# Logic.net
KiCad netlist of a schematic drawn in Altium Designer
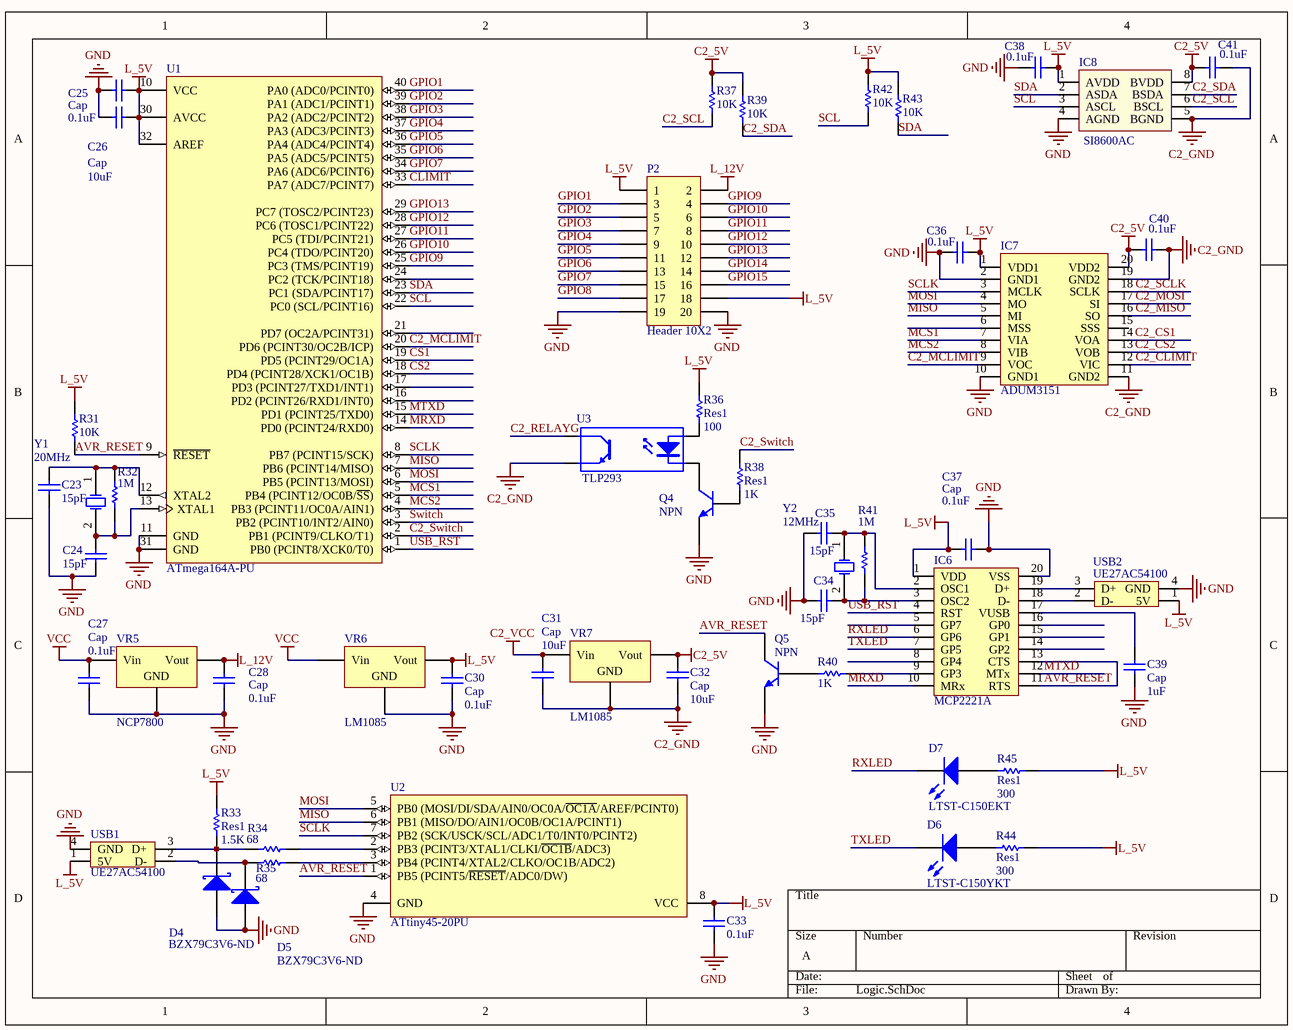
[diagram p0: Logic.SchDoc]

(export (version "E")
  (design (tool "Eeschema 10.0.6"))
  (components
    (comp (ref "C23")
      (value "15pF")
      (footprint "RAD-0.1")
      (description "Capacitor")
      (fields (field (name "Comment") "Cap") (field (name "PUBLISHER") "Altium Limited"))
      (libsource (lib "Miscellaneous Devices") (part "Cap"))
    )
    (comp (ref "C24")
      (value "15pF")
      (footprint "RAD-0.1")
      (description "Capacitor")
      (fields (field (name "Comment") "Cap") (field (name "PUBLISHER") "Altium Limited"))
      (libsource (lib "Miscellaneous Devices") (part "Cap"))
    )
    (comp (ref "C25")
      (value "Cap")
      (footprint "RAD-0.1")
      (description "Capacitor")
      (fields (field (name "ALTIUM_VALUE") "0.1uF") (field (name "PUBLISHER") "Altium Limited"))
      (libsource (lib "Miscellaneous Devices") (part "Cap"))
    )
    (comp (ref "C26")
      (value "Cap")
      (footprint "RAD-0.2")
      (description "Capacitor")
      (fields (field (name "ALTIUM_VALUE") "10uF") (field (name "PUBLISHER") "Altium Limited"))
      (libsource (lib "Miscellaneous Devices") (part "Cap"))
    )
    (comp (ref "C27")
      (value "Cap")
      (footprint "RAD-0.1")
      (description "Capacitor")
      (fields (field (name "ALTIUM_VALUE") "0.1uF") (field (name "PUBLISHER") "Altium Limited"))
      (libsource (lib "Miscellaneous Devices") (part "Cap"))
    )
    (comp (ref "C28")
      (value "Cap")
      (footprint "RAD-0.1")
      (description "Capacitor")
      (fields (field (name "ALTIUM_VALUE") "0.1uF") (field (name "PUBLISHER") "Altium Limited"))
      (libsource (lib "Miscellaneous Devices") (part "Cap"))
    )
    (comp (ref "C30")
      (value "Cap")
      (footprint "RAD-0.1")
      (description "Capacitor")
      (fields (field (name "ALTIUM_VALUE") "0.1uF") (field (name "PUBLISHER") "Altium Limited"))
      (libsource (lib "Power Supply Library") (part "Cap"))
    )
    (comp (ref "C31")
      (value "Cap")
      (footprint "RAD-0.1")
      (description "Capacitor")
      (fields (field (name "ALTIUM_VALUE") "10uF") (field (name "PUBLISHER") "Altium Limited"))
      (libsource (lib "Miscellaneous Devices") (part "Cap"))
    )
    (comp (ref "C32")
      (value "Cap")
      (footprint "RAD-0.1")
      (description "Capacitor")
      (fields (field (name "ALTIUM_VALUE") "10uF") (field (name "PUBLISHER") "Altium Limited"))
      (libsource (lib "Power Supply Library") (part "Cap"))
    )
    (comp (ref "C33")
      (value "0.1uF")
      (footprint "RAD-0.1")
      (description "Capacitor")
      (fields (field (name "Comment") "Cap") (field (name "PUBLISHER") "Altium Limited"))
      (libsource (lib "Miscellaneous Devices") (part "Cap"))
    )
    (comp (ref "C34")
      (value "15pF")
      (footprint "RAD-0.1")
      (description "Capacitor")
      (fields (field (name "Comment") "Cap") (field (name "PUBLISHER") "Altium Limited"))
      (libsource (lib "Miscellaneous Devices") (part "Cap"))
    )
    (comp (ref "C35")
      (value "15pF")
      (footprint "RAD-0.1")
      (description "Capacitor")
      (fields (field (name "Comment") "Cap") (field (name "PUBLISHER") "Altium Limited"))
      (libsource (lib "Miscellaneous Devices") (part "Cap"))
    )
    (comp (ref "C36")
      (value "0.1uF")
      (footprint "RAD-0.1")
      (description "Capacitor")
      (fields (field (name "Comment") "Cap") (field (name "PUBLISHER") "Altium Limited"))
      (libsource (lib "Miscellaneous Devices") (part "Cap"))
    )
    (comp (ref "C37")
      (value "Cap")
      (footprint "RAD-0.1")
      (description "Capacitor")
      (fields (field (name "ALTIUM_VALUE") "0.1uF") (field (name "PUBLISHER") "Altium Limited"))
      (libsource (lib "Miscellaneous Devices") (part "Cap"))
    )
    (comp (ref "C38")
      (value "0.1uF")
      (footprint "RAD-0.1")
      (description "Capacitor")
      (fields (field (name "Comment") "Cap") (field (name "PUBLISHER") "Altium Limited"))
      (libsource (lib "Miscellaneous Devices") (part "Cap"))
    )
    (comp (ref "C39")
      (value "Cap")
      (footprint "RAD-0.1")
      (description "Capacitor")
      (fields (field (name "ALTIUM_VALUE") "1uF") (field (name "PUBLISHER") "Altium Limited"))
      (libsource (lib "Miscellaneous Devices") (part "Cap"))
    )
    (comp (ref "C40")
      (value "0.1uF")
      (footprint "RAD-0.1")
      (description "Capacitor")
      (fields (field (name "Comment") "Cap") (field (name "PUBLISHER") "Altium Limited"))
      (libsource (lib "Miscellaneous Devices") (part "Cap"))
    )
    (comp (ref "C41")
      (value "0.1uF")
      (footprint "RAD-0.1")
      (description "Capacitor")
      (fields (field (name "Comment") "Cap") (field (name "PUBLISHER") "Altium Limited"))
      (libsource (lib "Miscellaneous Devices") (part "Cap"))
    )
    (comp (ref "D4")
      (value "BZX79C3V6-ND")
      (footprint "DO-35")
      (description "Schottky Diode")
      (fields (field (name "PUBLISHER") "Altium Limited"))
      (libsource (lib "Miscellaneous Devices") (part "D Schottky"))
    )
    (comp (ref "D5")
      (value "BZX79C3V6-ND")
      (footprint "DO-35")
      (description "Schottky Diode")
      (fields (field (name "PUBLISHER") "Altium Limited"))
      (libsource (lib "Miscellaneous Devices") (part "D Schottky"))
    )
    (comp (ref "D6")
      (value "LTST-C150YKT")
      (footprint "3.2X1.6X1.1")
      (description "Typical RED, GREEN, YELLOW, AMBER GaAs LED")
      (fields (field (name "PUBLISHER") "Altium Limited"))
      (libsource (lib "Power Supply Library") (part "LED2"))
    )
    (comp (ref "D7")
      (value "LTST-C150EKT")
      (footprint "3.2X1.6X1.1")
      (description "Typical RED, GREEN, YELLOW, AMBER GaAs LED")
      (fields (field (name "PUBLISHER") "Altium Limited"))
      (libsource (lib "Power Supply Library") (part "LED2"))
    )
    (comp (ref "IC6")
      (value "MCP2221A")
      (footprint "20-SO")
      (libsource (lib "Power Supply Library") (part "USB To UART"))
    )
    (comp (ref "IC7")
      (value "ADUM3151")
      (footprint "20-SSOP")
      (libsource (lib "Power Supply Library") (part "SPI Isolator"))
    )
    (comp (ref "IC8")
      (value "SI8600AC")
      (footprint "8-SO")
      (libsource (lib "Power Supply Library") (part "I2C Isolator"))
    )
    (comp (ref "P2")
      (value "Header 10X2")
      (footprint "HDR2X10")
      (description "Header, 10-Pin, Dual row")
      (fields (field (name "PUBLISHER") "Altium Limited"))
      (libsource (lib "Miscellaneous Connectors") (part "Header 10X2"))
    )
    (comp (ref "Q4")
      (value "NPN")
      (footprint "TO-226-AA")
      (description "NPN Bipolar Transistor")
      (fields (field (name "PUBLISHER") "Altium Limited"))
      (libsource (lib "Power Supply Library") (part "NPN"))
    )
    (comp (ref "Q5")
      (value "NPN")
      (footprint "TO-226-AA")
      (description "NPN Bipolar Transistor")
      (fields (field (name "PUBLISHER") "Altium Limited"))
      (libsource (lib "Power Supply Library") (part "NPN"))
    )
    (comp (ref "R31")
      (value "10K")
      (footprint "AXIAL-0.3")
      (description "Resistor")
      (fields (field (name "Comment") "Res1") (field (name "PUBLISHER") "Altium Limited"))
      (libsource (lib "Miscellaneous Devices") (part "Res1"))
    )
    (comp (ref "R32")
      (value "1M")
      (footprint "AXIAL-0.3")
      (description "Resistor")
      (fields (field (name "Comment") "Res1") (field (name "PUBLISHER") "Altium Limited"))
      (libsource (lib "Power Supply Library") (part "Res1"))
    )
    (comp (ref "R33")
      (value "Res1")
      (footprint "AXIAL-0.3")
      (description "Resistor")
      (fields (field (name "ALTIUM_VALUE") "1.5K") (field (name "PUBLISHER") "Altium Limited"))
      (libsource (lib "Power Supply Library") (part "Res1"))
    )
    (comp (ref "R34")
      (value "68")
      (footprint "AXIAL-0.3")
      (description "Resistor")
      (fields (field (name "Comment") "Res1") (field (name "PUBLISHER") "Altium Limited"))
      (libsource (lib "Power Supply Library") (part "Res1"))
    )
    (comp (ref "R35")
      (value "68")
      (footprint "AXIAL-0.3")
      (description "Resistor")
      (fields (field (name "Comment") "Res1") (field (name "PUBLISHER") "Altium Limited"))
      (libsource (lib "Power Supply Library") (part "Res1"))
    )
    (comp (ref "R36")
      (value "Res1")
      (footprint "AXIAL-0.3")
      (description "Resistor")
      (fields (field (name "ALTIUM_VALUE") "100") (field (name "PUBLISHER") "Altium Limited"))
      (libsource (lib "Power Supply Library") (part "Res1"))
    )
    (comp (ref "R37")
      (value "10K")
      (footprint "AXIAL-0.3")
      (description "Resistor")
      (fields (field (name "Comment") "Res1") (field (name "PUBLISHER") "Altium Limited"))
      (libsource (lib "Power Supply Library") (part "Res1"))
    )
    (comp (ref "R38")
      (value "Res1")
      (footprint "AXIAL-0.3")
      (description "Resistor")
      (fields (field (name "ALTIUM_VALUE") "1K") (field (name "PUBLISHER") "Altium Limited"))
      (libsource (lib "Power Supply Library") (part "Res1"))
    )
    (comp (ref "R39")
      (value "10K")
      (footprint "AXIAL-0.3")
      (description "Resistor")
      (fields (field (name "Comment") "Res1") (field (name "PUBLISHER") "Altium Limited"))
      (libsource (lib "Power Supply Library") (part "Res1"))
    )
    (comp (ref "R40")
      (value "1K")
      (footprint "AXIAL-0.3")
      (description "Resistor")
      (fields (field (name "Comment") "Res1") (field (name "PUBLISHER") "Altium Limited"))
      (libsource (lib "Power Supply Library") (part "Res1"))
    )
    (comp (ref "R41")
      (value "1M")
      (footprint "AXIAL-0.3")
      (description "Resistor")
      (fields (field (name "Comment") "Res1") (field (name "PUBLISHER") "Altium Limited"))
      (libsource (lib "Power Supply Library") (part "Res1"))
    )
    (comp (ref "R42")
      (value "10K")
      (footprint "AXIAL-0.3")
      (description "Resistor")
      (fields (field (name "Comment") "Res1") (field (name "PUBLISHER") "Altium Limited"))
      (libsource (lib "Power Supply Library") (part "Res1"))
    )
    (comp (ref "R43")
      (value "10K")
      (footprint "AXIAL-0.3")
      (description "Resistor")
      (fields (field (name "Comment") "Res1") (field (name "PUBLISHER") "Altium Limited"))
      (libsource (lib "Power Supply Library") (part "Res1"))
    )
    (comp (ref "R44")
      (value "Res1")
      (footprint "AXIAL-0.3")
      (description "Resistor")
      (fields (field (name "ALTIUM_VALUE") "300") (field (name "PUBLISHER") "Altium Limited"))
      (libsource (lib "Power Supply Library") (part "Res1"))
    )
    (comp (ref "R45")
      (value "Res1")
      (footprint "AXIAL-0.3")
      (description "Resistor")
      (fields (field (name "ALTIUM_VALUE") "300") (field (name "PUBLISHER") "Altium Limited"))
      (libsource (lib "Power Supply Library") (part "Res1"))
    )
    (comp (ref "U1")
      (value "ATmega164A-PU")
      (footprint "40P6")
      (fields (field (name "PUBLISHER") "Altium Limited"))
      (libsource (lib "Atmel Microcontroller 8-Bit megaAVR") (part "ATmega164A-PU"))
    )
    (comp (ref "U2")
      (value "ATtiny45-20PU")
      (footprint "8P3")
      (fields (field (name "PUBLISHER") "Altium Limited"))
      (libsource (lib "Atmel Microcontroller 8-Bit tinyAVR") (part "ATtiny45-20PU"))
    )
    (comp (ref "U3")
      (value "TLP293")
      (footprint "2-SO")
      (description "4-Pin Phototransistor Optocoupler")
      (fields (field (name "PUBLISHER") "Altium Limited"))
      (libsource (lib "Power Supply Library") (part "Optoisolator1"))
    )
    (comp (ref "USB1") (value "UE27AC54100") (footprint "USB") (libsource (lib "") (part "USB_1")))
    (comp (ref "USB2")
      (value "UE27AC54100")
      (footprint "USB")
      (libsource (lib "Power Supply Library") (part "USB"))
    )
    (comp (ref "VR5")
      (value "NCP7800")
      (footprint "TO220")
      (libsource (lib "Power Supply Library") (part "Voltage Regulator 12V"))
    )
    (comp (ref "VR6")
      (value "LM1085")
      (footprint "TO220")
      (libsource (lib "Power Supply Library") (part "Voltage Regulator 5V"))
    )
    (comp (ref "VR7")
      (value "LM1085")
      (footprint "TO220")
      (libsource (lib "Power Supply Library") (part "Voltage Regulator 5V"))
    )
    (comp (ref "Y1")
      (value "20MHz")
      (footprint "R38")
      (description "Crystal Oscillator")
      (fields (field (name "PUBLISHER") "Altium Limited"))
      (libsource (lib "Miscellaneous Devices") (part "XTAL"))
    )
    (comp (ref "Y2")
      (value "12MHz")
      (footprint "R38")
      (description "Crystal Oscillator")
      (fields (field (name "PUBLISHER") "Altium Limited"))
      (libsource (lib "Miscellaneous Devices") (part "XTAL"))
    )
  )
  (nets
    (net (code "1") (name "/AVR_RESET") (class "Default")
      (node (ref "IC6") (pin "11") (pinfunction "RTS_11") (pintype "passive"))
      (node (ref "IC6") (pin "13") (pinfunction "CTS_13") (pintype "passive"))
      (node (ref "Q5") (pin "1") (pinfunction "C_1") (pintype "passive"))
      (node (ref "R31") (pin "1") (pinfunction "1_1") (pintype "passive"))
      (node (ref "U1") (pin "9") (pinfunction "~{RESET}_9") (pintype "input"))
      (node (ref "U2") (pin "1") (pinfunction "PB5_(PCINT5/~{RESET}/ADC0/DW)_1") (pintype "bidirectional"))
    )
    (net (code "2") (name "/C2_CLIMIT") (class "Default")
      (node (ref "IC7") (pin "12") (pinfunction "VIC_12") (pintype "passive"))
    )
    (net (code "3") (name "/C2_CS1") (class "Default")
      (node (ref "IC7") (pin "14") (pinfunction "VOA_14") (pintype "passive"))
    )
    (net (code "4") (name "/C2_CS2") (class "Default")
      (node (ref "IC7") (pin "13") (pinfunction "VOB_13") (pintype "passive"))
    )
    (net (code "5") (name "/C2_MCLIMIT") (class "Default")
      (node (ref "IC7") (pin "9") (pinfunction "VOC_9") (pintype "passive"))
      (node (ref "U1") (pin "20") (pinfunction "PD6_(PCINT30/OC2B/ICP)_20") (pintype "bidirectional"))
    )
    (net (code "6") (name "/C2_MISO") (class "Default")
      (node (ref "IC7") (pin "16") (pinfunction "SO_16") (pintype "passive"))
    )
    (net (code "7") (name "/C2_MOSI") (class "Default")
      (node (ref "IC7") (pin "17") (pinfunction "SI_17") (pintype "passive"))
    )
    (net (code "8") (name "/C2_RELAYG") (class "Default")
      (node (ref "U3") (pin "4") (pinfunction "C_4") (pintype "passive"))
    )
    (net (code "9") (name "/C2_SCL") (class "Default")
      (node (ref "IC8") (pin "6") (pinfunction "BSCL_6") (pintype "passive"))
      (node (ref "R37") (pin "1") (pinfunction "1_1") (pintype "passive"))
    )
    (net (code "10") (name "/C2_SCLK") (class "Default")
      (node (ref "IC7") (pin "18") (pinfunction "SCLK_18") (pintype "passive"))
    )
    (net (code "11") (name "/C2_SDA") (class "Default")
      (node (ref "IC8") (pin "7") (pinfunction "BSDA_7") (pintype "passive"))
      (node (ref "R39") (pin "1") (pinfunction "1_1") (pintype "passive"))
    )
    (net (code "12") (name "/C2_Switch") (class "Default")
      (node (ref "R38") (pin "1") (pinfunction "1_1") (pintype "passive"))
      (node (ref "U1") (pin "2") (pinfunction "PB1_(PCINT9/CLKO/T1)_2") (pintype "bidirectional"))
    )
    (net (code "13") (name "/CLIMIT") (class "Default")
      (node (ref "U1") (pin "33") (pinfunction "PA7_(ADC7/PCINT7)_33") (pintype "bidirectional"))
    )
    (net (code "14") (name "/CS1") (class "Default")
      (node (ref "U1") (pin "19") (pinfunction "PD5_(PCINT29/OC1A)_19") (pintype "bidirectional"))
    )
    (net (code "15") (name "/CS2") (class "Default")
      (node (ref "U1") (pin "18") (pinfunction "PD4_(PCINT28/XCK1/OC1B)_18") (pintype "bidirectional"))
    )
    (net (code "16") (name "/GPIO1") (class "Default")
      (node (ref "P2") (pin "3") (pinfunction "3_3") (pintype "passive"))
      (node (ref "U1") (pin "40") (pinfunction "PA0_(ADC0/PCINT0)_40") (pintype "bidirectional"))
    )
    (net (code "17") (name "/GPIO2") (class "Default")
      (node (ref "P2") (pin "5") (pinfunction "5_5") (pintype "passive"))
      (node (ref "U1") (pin "39") (pinfunction "PA1_(ADC1/PCINT1)_39") (pintype "bidirectional"))
    )
    (net (code "18") (name "/GPIO3") (class "Default")
      (node (ref "P2") (pin "7") (pinfunction "7_7") (pintype "passive"))
      (node (ref "U1") (pin "38") (pinfunction "PA2_(ADC2/PCINT2)_38") (pintype "bidirectional"))
    )
    (net (code "19") (name "/GPIO4") (class "Default")
      (node (ref "P2") (pin "9") (pinfunction "9_9") (pintype "passive"))
      (node (ref "U1") (pin "37") (pinfunction "PA3_(ADC3/PCINT3)_37") (pintype "bidirectional"))
    )
    (net (code "20") (name "/GPIO5") (class "Default")
      (node (ref "P2") (pin "11") (pinfunction "11_11") (pintype "passive"))
      (node (ref "U1") (pin "36") (pinfunction "PA4_(ADC4/PCINT4)_36") (pintype "bidirectional"))
    )
    (net (code "21") (name "/GPIO6") (class "Default")
      (node (ref "P2") (pin "13") (pinfunction "13_13") (pintype "passive"))
      (node (ref "U1") (pin "35") (pinfunction "PA5_(ADC5/PCINT5)_35") (pintype "bidirectional"))
    )
    (net (code "22") (name "/GPIO7") (class "Default")
      (node (ref "P2") (pin "15") (pinfunction "15_15") (pintype "passive"))
      (node (ref "U1") (pin "34") (pinfunction "PA6_(ADC6/PCINT6)_34") (pintype "bidirectional"))
    )
    (net (code "23") (name "/GPIO8") (class "Default")
      (node (ref "P2") (pin "17") (pinfunction "17_17") (pintype "passive"))
    )
    (net (code "24") (name "/GPIO9") (class "Default")
      (node (ref "P2") (pin "4") (pinfunction "4_4") (pintype "passive"))
      (node (ref "U1") (pin "25") (pinfunction "PC3_(TMS/PCINT19)_25") (pintype "bidirectional"))
    )
    (net (code "25") (name "/GPIO10") (class "Default")
      (node (ref "P2") (pin "6") (pinfunction "6_6") (pintype "passive"))
      (node (ref "U1") (pin "26") (pinfunction "PC4_(TDO/PCINT20)_26") (pintype "bidirectional"))
    )
    (net (code "26") (name "/GPIO11") (class "Default")
      (node (ref "P2") (pin "8") (pinfunction "8_8") (pintype "passive"))
      (node (ref "U1") (pin "27") (pinfunction "PC5_(TDI/PCINT21)_27") (pintype "bidirectional"))
    )
    (net (code "27") (name "/GPIO12") (class "Default")
      (node (ref "P2") (pin "10") (pinfunction "10_10") (pintype "passive"))
      (node (ref "U1") (pin "28") (pinfunction "PC6_(TOSC1/PCINT22)_28") (pintype "bidirectional"))
    )
    (net (code "28") (name "/GPIO13") (class "Default")
      (node (ref "P2") (pin "12") (pinfunction "12_12") (pintype "passive"))
      (node (ref "U1") (pin "29") (pinfunction "PC7_(TOSC2/PCINT23)_29") (pintype "bidirectional"))
    )
    (net (code "29") (name "/GPIO14") (class "Default")
      (node (ref "P2") (pin "14") (pinfunction "14_14") (pintype "passive"))
    )
    (net (code "30") (name "/GPIO15") (class "Default")
      (node (ref "P2") (pin "16") (pinfunction "16_16") (pintype "passive"))
    )
    (net (code "31") (name "/MCS1") (class "Default")
      (node (ref "IC7") (pin "7") (pinfunction "VIA_7") (pintype "passive"))
      (node (ref "U1") (pin "5") (pinfunction "PB4_(PCINT12/OC0B/~{SS})_5") (pintype "bidirectional"))
    )
    (net (code "32") (name "/MCS2") (class "Default")
      (node (ref "IC7") (pin "8") (pinfunction "VIB_8") (pintype "passive"))
      (node (ref "U1") (pin "4") (pinfunction "PB3_(PCINT11/OC0A/AIN1)_4") (pintype "bidirectional"))
    )
    (net (code "33") (name "/MISO") (class "Default")
      (node (ref "IC7") (pin "5") (pinfunction "MI_5") (pintype "passive"))
      (node (ref "U1") (pin "7") (pinfunction "PB6_(PCINT14/MISO)_7") (pintype "bidirectional"))
      (node (ref "U2") (pin "6") (pinfunction "PB1_(MISO/DO/AIN1/OC0B/OC1A/PCINT1)_6") (pintype "bidirectional"))
    )
    (net (code "34") (name "/MOSI") (class "Default")
      (node (ref "IC7") (pin "4") (pinfunction "MO_4") (pintype "passive"))
      (node (ref "U1") (pin "6") (pinfunction "PB5_(PCINT13/MOSI)_6") (pintype "bidirectional"))
      (node (ref "U2") (pin "5") (pinfunction "PB0_(MOSI/DI/SDA/AIN0/OC0A/~{OC1A}/AREF/PCINT0)_5") (pintype "bidirectional"))
    )
    (net (code "35") (name "/MRXD") (class "Default")
      (node (ref "IC6") (pin "10") (pinfunction "MRx_10") (pintype "passive"))
      (node (ref "U1") (pin "14") (pinfunction "PD0_(PCINT24/RXD0)_14") (pintype "bidirectional"))
    )
    (net (code "36") (name "/MTXD") (class "Default")
      (node (ref "IC6") (pin "12") (pinfunction "MTx_12") (pintype "passive"))
      (node (ref "U1") (pin "15") (pinfunction "PD1_(PCINT25/TXD0)_15") (pintype "bidirectional"))
    )
    (net (code "37") (name "/RXLED") (class "Default")
      (node (ref "D7") (pin "2") (pinfunction "K_2") (pintype "passive"))
      (node (ref "IC6") (pin "6") (pinfunction "GP6_6") (pintype "passive"))
    )
    (net (code "38") (name "/SCL") (class "Default")
      (node (ref "IC8") (pin "3") (pinfunction "ASCL_3") (pintype "passive"))
      (node (ref "R42") (pin "1") (pinfunction "1_1") (pintype "passive"))
      (node (ref "U1") (pin "22") (pinfunction "PC0_(SCL/PCINT16)_22") (pintype "bidirectional"))
    )
    (net (code "39") (name "/SCLK") (class "Default")
      (node (ref "IC7") (pin "3") (pinfunction "MCLK_3") (pintype "passive"))
      (node (ref "U1") (pin "8") (pinfunction "PB7_(PCINT15/SCK)_8") (pintype "bidirectional"))
      (node (ref "U2") (pin "7") (pinfunction "PB2_(SCK/USCK/SCL/ADC1/T0/INT0/PCINT2)_7") (pintype "bidirectional"))
    )
    (net (code "40") (name "/SDA") (class "Default")
      (node (ref "IC8") (pin "2") (pinfunction "ASDA_2") (pintype "passive"))
      (node (ref "R43") (pin "1") (pinfunction "1_1") (pintype "passive"))
      (node (ref "U1") (pin "23") (pinfunction "PC1_(SDA/PCINT17)_23") (pintype "bidirectional"))
    )
    (net (code "41") (name "/Switch") (class "Default")
      (node (ref "U1") (pin "3") (pinfunction "PB2_(PCINT10/INT2/AIN0)_3") (pintype "bidirectional"))
    )
    (net (code "42") (name "/TXLED") (class "Default")
      (node (ref "D6") (pin "2") (pinfunction "K_2") (pintype "passive"))
      (node (ref "IC6") (pin "7") (pinfunction "GP5_7") (pintype "passive"))
    )
    (net (code "43") (name "/USB_RST") (class "Default")
      (node (ref "IC6") (pin "4") (pinfunction "RST_4") (pintype "passive"))
      (node (ref "U1") (pin "1") (pinfunction "PB0_(PCINT8/XCK0/T0)_1") (pintype "bidirectional"))
    )
    (net (code "44") (name "C2_5V") (class "Default")
      (node (ref "C32") (pin "2") (pinfunction "2_2") (pintype "passive"))
      (node (ref "C40") (pin "2") (pinfunction "2_2") (pintype "passive"))
      (node (ref "C41") (pin "1") (pinfunction "1_1") (pintype "passive"))
      (node (ref "IC7") (pin "20") (pinfunction "VDD2_20") (pintype "passive"))
      (node (ref "IC8") (pin "8") (pinfunction "BVDD_8") (pintype "passive"))
      (node (ref "R37") (pin "2") (pinfunction "2_2") (pintype "passive"))
      (node (ref "R39") (pin "2") (pinfunction "2_2") (pintype "passive"))
      (node (ref "VR7") (pin "3") (pinfunction "Vout_3") (pintype "passive"))
    )
    (net (code "45") (name "C2_GND") (class "Default")
      (node (ref "C31") (pin "1") (pinfunction "1_1") (pintype "passive"))
      (node (ref "C32") (pin "1") (pinfunction "1_1") (pintype "passive"))
      (node (ref "C40") (pin "1") (pinfunction "1_1") (pintype "passive"))
      (node (ref "C41") (pin "2") (pinfunction "2_2") (pintype "passive"))
      (node (ref "IC7") (pin "11") (pinfunction "GND2_11") (pintype "passive"))
      (node (ref "IC7") (pin "19") (pinfunction "GND2_19") (pintype "passive"))
      (node (ref "IC8") (pin "5") (pinfunction "BGND_5") (pintype "passive"))
      (node (ref "U3") (pin "3") (pinfunction "E_3") (pintype "passive"))
      (node (ref "VR7") (pin "2") (pinfunction "GND_2") (pintype "passive"))
    )
    (net (code "46") (name "C2_VCC") (class "Default")
      (node (ref "C31") (pin "2") (pinfunction "2_2") (pintype "passive"))
      (node (ref "VR7") (pin "1") (pinfunction "Vin_1") (pintype "passive"))
    )
    (net (code "47") (name "GND") (class "Default")
      (node (ref "C23") (pin "2") (pinfunction "2_2") (pintype "passive"))
      (node (ref "C24") (pin "2") (pinfunction "2_2") (pintype "passive"))
      (node (ref "C25") (pin "1") (pinfunction "1_1") (pintype "passive"))
      (node (ref "C26") (pin "1") (pinfunction "1_1") (pintype "passive"))
      (node (ref "C27") (pin "1") (pinfunction "1_1") (pintype "passive"))
      (node (ref "C28") (pin "1") (pinfunction "1_1") (pintype "passive"))
      (node (ref "C30") (pin "1") (pinfunction "1_1") (pintype "passive"))
      (node (ref "C33") (pin "1") (pinfunction "1_1") (pintype "passive"))
      (node (ref "C34") (pin "1") (pinfunction "1_1") (pintype "passive"))
      (node (ref "C35") (pin "1") (pinfunction "1_1") (pintype "passive"))
      (node (ref "C36") (pin "1") (pinfunction "1_1") (pintype "passive"))
      (node (ref "C37") (pin "2") (pinfunction "2_2") (pintype "passive"))
      (node (ref "C38") (pin "1") (pinfunction "1_1") (pintype "passive"))
      (node (ref "C39") (pin "1") (pinfunction "1_1") (pintype "passive"))
      (node (ref "D4") (pin "1") (pinfunction "A_1") (pintype "passive"))
      (node (ref "D5") (pin "1") (pinfunction "A_1") (pintype "passive"))
      (node (ref "IC6") (pin "20") (pinfunction "VSS_20") (pintype "passive"))
      (node (ref "IC7") (pin "10") (pinfunction "GND1_10") (pintype "passive"))
      (node (ref "IC7") (pin "2") (pinfunction "GND1_2") (pintype "passive"))
      (node (ref "IC8") (pin "4") (pinfunction "AGND_4") (pintype "passive"))
      (node (ref "P2") (pin "19") (pinfunction "19_19") (pintype "passive"))
      (node (ref "P2") (pin "20") (pinfunction "20_20") (pintype "passive"))
      (node (ref "Q4") (pin "3") (pinfunction "E_3") (pintype "passive"))
      (node (ref "Q5") (pin "3") (pinfunction "E_3") (pintype "passive"))
      (node (ref "U1") (pin "11") (pinfunction "GND_11") (pintype "power_in"))
      (node (ref "U1") (pin "31") (pinfunction "GND_31") (pintype "power_in"))
      (node (ref "U2") (pin "4") (pinfunction "GND_4") (pintype "power_in"))
      (node (ref "USB1") (pin "4") (pinfunction "GND_4") (pintype "passive"))
      (node (ref "USB2") (pin "4") (pinfunction "GND_4") (pintype "passive"))
      (node (ref "VR5") (pin "2") (pinfunction "GND_2") (pintype "passive"))
      (node (ref "VR6") (pin "2") (pinfunction "GND_2") (pintype "passive"))
    )
    (net (code "48") (name "L_5V") (class "Default")
      (node (ref "C25") (pin "2") (pinfunction "2_2") (pintype "passive"))
      (node (ref "C26") (pin "2") (pinfunction "2_2") (pintype "passive"))
      (node (ref "C30") (pin "2") (pinfunction "2_2") (pintype "passive"))
      (node (ref "C33") (pin "2") (pinfunction "2_2") (pintype "passive"))
      (node (ref "C36") (pin "2") (pinfunction "2_2") (pintype "passive"))
      (node (ref "C37") (pin "1") (pinfunction "1_1") (pintype "passive"))
      (node (ref "C38") (pin "2") (pinfunction "2_2") (pintype "passive"))
      (node (ref "IC6") (pin "1") (pinfunction "VDD_1") (pintype "passive"))
      (node (ref "IC7") (pin "1") (pinfunction "VDD1_1") (pintype "passive"))
      (node (ref "IC8") (pin "1") (pinfunction "AVDD_1") (pintype "passive"))
      (node (ref "P2") (pin "1") (pinfunction "1_1") (pintype "passive"))
      (node (ref "P2") (pin "18") (pinfunction "18_18") (pintype "passive"))
      (node (ref "R31") (pin "2") (pinfunction "2_2") (pintype "passive"))
      (node (ref "R33") (pin "1") (pinfunction "1_1") (pintype "passive"))
      (node (ref "R36") (pin "2") (pinfunction "2_2") (pintype "passive"))
      (node (ref "R42") (pin "2") (pinfunction "2_2") (pintype "passive"))
      (node (ref "R43") (pin "2") (pinfunction "2_2") (pintype "passive"))
      (node (ref "R44") (pin "2") (pinfunction "2_2") (pintype "passive"))
      (node (ref "R45") (pin "2") (pinfunction "2_2") (pintype "passive"))
      (node (ref "U1") (pin "10") (pinfunction "VCC_10") (pintype "power_in"))
      (node (ref "U1") (pin "30") (pinfunction "AVCC_30") (pintype "power_in"))
      (node (ref "U1") (pin "32") (pinfunction "AREF_32") (pintype "power_in"))
      (node (ref "U2") (pin "8") (pinfunction "VCC_8") (pintype "power_in"))
      (node (ref "USB1") (pin "1") (pinfunction "5V_1") (pintype "passive"))
      (node (ref "USB2") (pin "1") (pinfunction "5V_1") (pintype "passive"))
      (node (ref "VR6") (pin "3") (pinfunction "Vout_3") (pintype "passive"))
    )
    (net (code "49") (name "L_12V") (class "Default")
      (node (ref "C28") (pin "2") (pinfunction "2_2") (pintype "passive"))
      (node (ref "P2") (pin "2") (pinfunction "2_2") (pintype "passive"))
      (node (ref "VR5") (pin "3") (pinfunction "Vout_3") (pintype "passive"))
    )
    (net (code "50") (name "Net-(D4-K)") (class "Default")
      (node (ref "D4") (pin "2") (pinfunction "K_2") (pintype "passive"))
      (node (ref "R33") (pin "2") (pinfunction "2_2") (pintype "passive"))
      (node (ref "R34") (pin "2") (pinfunction "2_2") (pintype "passive"))
      (node (ref "USB1") (pin "3") (pinfunction "D+_3") (pintype "passive"))
    )
    (net (code "51") (name "Net-(D5-K)") (class "Default")
      (node (ref "D5") (pin "2") (pinfunction "K_2") (pintype "passive"))
      (node (ref "R35") (pin "2") (pinfunction "2_2") (pintype "passive"))
      (node (ref "USB1") (pin "2") (pinfunction "D-_2") (pintype "passive"))
    )
    (net (code "52") (name "Net-(D6-A)") (class "Default")
      (node (ref "D6") (pin "1") (pinfunction "A_1") (pintype "passive"))
      (node (ref "R44") (pin "1") (pinfunction "1_1") (pintype "passive"))
    )
    (net (code "53") (name "Net-(D7-A)") (class "Default")
      (node (ref "D7") (pin "1") (pinfunction "A_1") (pintype "passive"))
      (node (ref "R45") (pin "1") (pinfunction "1_1") (pintype "passive"))
    )
    (net (code "54") (name "Net-(IC6-D+)") (class "Default")
      (node (ref "IC6") (pin "19") (pinfunction "D+_19") (pintype "passive"))
      (node (ref "USB2") (pin "3") (pinfunction "D+_3") (pintype "passive"))
    )
    (net (code "55") (name "Net-(IC6-D-)") (class "Default")
      (node (ref "IC6") (pin "18") (pinfunction "D-_18") (pintype "passive"))
      (node (ref "USB2") (pin "2") (pinfunction "D-_2") (pintype "passive"))
    )
    (net (code "56") (name "Net-(IC6-GP3)") (class "Default")
      (node (ref "IC6") (pin "9") (pinfunction "GP3_9") (pintype "passive"))
      (node (ref "R40") (pin "2") (pinfunction "2_2") (pintype "passive"))
    )
    (net (code "57") (name "Net-(IC6-OSC1)") (class "Default")
      (node (ref "C35") (pin "2") (pinfunction "2_2") (pintype "passive"))
      (node (ref "IC6") (pin "2") (pinfunction "OSC1_2") (pintype "passive"))
      (node (ref "R41") (pin "1") (pinfunction "1_1") (pintype "passive"))
      (node (ref "Y2") (pin "1") (pinfunction "OSC1_1") (pintype "passive"))
    )
    (net (code "58") (name "Net-(IC6-OSC2)") (class "Default")
      (node (ref "C34") (pin "2") (pinfunction "2_2") (pintype "passive"))
      (node (ref "IC6") (pin "3") (pinfunction "OSC2_3") (pintype "passive"))
      (node (ref "R41") (pin "2") (pinfunction "2_2") (pintype "passive"))
      (node (ref "Y2") (pin "2") (pinfunction "OSC2_2") (pintype "passive"))
    )
    (net (code "59") (name "Net-(IC6-VUSB)") (class "Default")
      (node (ref "C39") (pin "2") (pinfunction "2_2") (pintype "passive"))
      (node (ref "IC6") (pin "17") (pinfunction "VUSB_17") (pintype "passive"))
    )
    (net (code "60") (name "Net-(Q4-B)") (class "Default")
      (node (ref "Q4") (pin "2") (pinfunction "B_2") (pintype "passive"))
      (node (ref "R38") (pin "2") (pinfunction "2_2") (pintype "passive"))
    )
    (net (code "61") (name "Net-(Q4-C)") (class "Default")
      (node (ref "Q4") (pin "1") (pinfunction "C_1") (pintype "passive"))
      (node (ref "U3") (pin "2") (pinfunction "K_2") (pintype "passive"))
    )
    (net (code "62") (name "Net-(Q5-B)") (class "Default")
      (node (ref "Q5") (pin "2") (pinfunction "B_2") (pintype "passive"))
      (node (ref "R40") (pin "1") (pinfunction "1_1") (pintype "passive"))
    )
    (net (code "63") (name "Net-(U1-XTAL1)") (class "Default")
      (node (ref "C24") (pin "1") (pinfunction "1_1") (pintype "passive"))
      (node (ref "R32") (pin "2") (pinfunction "2_2") (pintype "passive"))
      (node (ref "U1") (pin "13") (pinfunction "XTAL1_13") (pintype "input"))
      (node (ref "Y1") (pin "2") (pinfunction "OSC2_2") (pintype "passive"))
    )
    (net (code "64") (name "Net-(U1-XTAL2)") (class "Default")
      (node (ref "C23") (pin "1") (pinfunction "1_1") (pintype "passive"))
      (node (ref "R32") (pin "1") (pinfunction "1_1") (pintype "passive"))
      (node (ref "U1") (pin "12") (pinfunction "XTAL2_12") (pintype "output"))
      (node (ref "Y1") (pin "1") (pinfunction "OSC1_1") (pintype "passive"))
    )
    (net (code "65") (name "Net-(U2-PB3_(PCINT3{slash}XTAL1{slash}CLKI{slash}~{OC1B}{slash}ADC3))") (class "Default")
      (node (ref "R34") (pin "1") (pinfunction "1_1") (pintype "passive"))
      (node (ref "U2") (pin "2") (pinfunction "PB3_(PCINT3/XTAL1/CLKI/~{OC1B}/ADC3)_2") (pintype "bidirectional"))
    )
    (net (code "66") (name "Net-(U2-PB4_(PCINT4{slash}XTAL2{slash}CLKO{slash}OC1B{slash}ADC2))") (class "Default")
      (node (ref "R35") (pin "1") (pinfunction "1_1") (pintype "passive"))
      (node (ref "U2") (pin "3") (pinfunction "PB4_(PCINT4/XTAL2/CLKO/OC1B/ADC2)_3") (pintype "bidirectional"))
    )
    (net (code "67") (name "Net-(U3-A)") (class "Default")
      (node (ref "R36") (pin "1") (pinfunction "1_1") (pintype "passive"))
      (node (ref "U3") (pin "1") (pinfunction "A_1") (pintype "passive"))
    )
    (net (code "68") (name "VCC") (class "Default")
      (node (ref "C27") (pin "2") (pinfunction "2_2") (pintype "passive"))
      (node (ref "VR5") (pin "1") (pinfunction "Vin_1") (pintype "passive"))
      (node (ref "VR6") (pin "1") (pinfunction "Vin_1") (pintype "passive"))
    )
    (net (code "69") (name "unconnected-(IC6-GP0-Pad16)") (class "Default")
      (node (ref "IC6") (pin "16") (pinfunction "GP0_16") (pintype "passive"))
    )
    (net (code "70") (name "unconnected-(IC6-GP1-Pad15)") (class "Default")
      (node (ref "IC6") (pin "15") (pinfunction "GP1_15") (pintype "passive"))
    )
    (net (code "71") (name "unconnected-(IC6-GP2-Pad14)") (class "Default")
      (node (ref "IC6") (pin "14") (pinfunction "GP2_14") (pintype "passive"))
    )
    (net (code "72") (name "unconnected-(IC6-GP4-Pad8)") (class "Default")
      (node (ref "IC6") (pin "8") (pinfunction "GP4_8") (pintype "passive"))
    )
    (net (code "73") (name "unconnected-(IC6-GP7-Pad5)") (class "Default")
      (node (ref "IC6") (pin "5") (pinfunction "GP7_5") (pintype "passive"))
    )
    (net (code "74") (name "unconnected-(IC7-MSS-Pad6)") (class "Default")
      (node (ref "IC7") (pin "6") (pinfunction "MSS_6") (pintype "passive"))
    )
    (net (code "75") (name "unconnected-(IC7-SSS-Pad15)") (class "Default")
      (node (ref "IC7") (pin "15") (pinfunction "SSS_15") (pintype "passive"))
    )
    (net (code "76") (name "unconnected-(U1-PC2_(TCK{slash}PCINT18)-Pad24)") (class "Default")
      (node (ref "U1") (pin "24") (pinfunction "PC2_(TCK/PCINT18)_24") (pintype "bidirectional"))
    )
    (net (code "77") (name "unconnected-(U1-PD2_(PCINT26{slash}RXD1{slash}INT0)-Pad16)") (class "Default")
      (node (ref "U1") (pin "16") (pinfunction "PD2_(PCINT26/RXD1/INT0)_16") (pintype "bidirectional"))
    )
    (net (code "78") (name "unconnected-(U1-PD3_(PCINT27{slash}TXD1{slash}INT1)-Pad17)") (class "Default")
      (node (ref "U1") (pin "17") (pinfunction "PD3_(PCINT27/TXD1/INT1)_17") (pintype "bidirectional"))
    )
    (net (code "79") (name "unconnected-(U1-PD7_(OC2A{slash}PCINT31)-Pad21)") (class "Default")
      (node (ref "U1") (pin "21") (pinfunction "PD7_(OC2A/PCINT31)_21") (pintype "bidirectional"))
    )
  )
)
